# probe.net
KiCad netlist of a schematic drawn in EAGLE
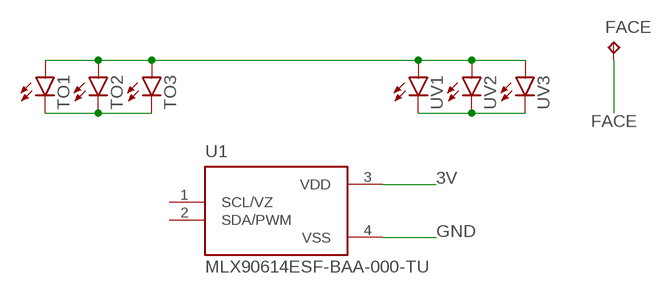
[diagram p0: schematic, sheet 1]

(export (version "E")
  (design (tool "Eeschema 10.0.6"))
  (components
    (comp (ref "FACE")
      (value "TPTP14R")
      (footprint "eagle-import:TP14R")
      (libsource (lib "eagle-import") (part "TPTP14R"))
    )
    (comp (ref "TO1")
      (value "LED5MM")
      (footprint "eagle-import:LED5MM")
      (libsource (lib "eagle-import") (part "LED5MM"))
    )
    (comp (ref "TO2")
      (value "LED5MM")
      (footprint "eagle-import:LED5MM")
      (libsource (lib "eagle-import") (part "LED5MM"))
    )
    (comp (ref "TO3")
      (value "LED5MM")
      (footprint "eagle-import:LED5MM")
      (libsource (lib "eagle-import") (part "LED5MM"))
    )
    (comp (ref "U1")
      (value "MLX90614ESF-BAA-000-TU")
      (footprint "eagle-import:TO254P942H425-4")
      (fields (field (name "MF") "Melexis"))
      (libsource (lib "eagle-import") (part "MLX90614ESF-BAA-000-TU"))
    )
    (comp (ref "UV1")
      (value "LED5MM")
      (footprint "eagle-import:LED5MM")
      (libsource (lib "eagle-import") (part "LED5MM"))
    )
    (comp (ref "UV2")
      (value "LED5MM")
      (footprint "eagle-import:LED5MM")
      (libsource (lib "eagle-import") (part "LED5MM"))
    )
    (comp (ref "UV3")
      (value "LED5MM")
      (footprint "eagle-import:LED5MM")
      (libsource (lib "eagle-import") (part "LED5MM"))
    )
  )
  (nets
    (net (code "1") (name "/3V") (class "Default")
      (node (ref "TO1") (pin "A") (pinfunction "A_A") (pintype "passive"))
      (node (ref "TO2") (pin "A") (pinfunction "A_A") (pintype "passive"))
      (node (ref "TO3") (pin "A") (pinfunction "A_A") (pintype "passive"))
      (node (ref "U1") (pin "3") (pinfunction "VDD_3") (pintype "power_in"))
      (node (ref "UV1") (pin "A") (pinfunction "A_A") (pintype "passive"))
      (node (ref "UV2") (pin "A") (pinfunction "A_A") (pintype "passive"))
      (node (ref "UV3") (pin "A") (pinfunction "A_A") (pintype "passive"))
    )
    (net (code "2") (name "/FACE") (class "Default")
      (node (ref "FACE") (pin "TP") (pinfunction "TP_TP") (pintype "input"))
    )
    (net (code "3") (name "/GND") (class "Default")
      (node (ref "U1") (pin "4") (pinfunction "VSS_4") (pintype "power_in"))
    )
    (net (code "4") (name "Net-(TO1-C)") (class "Default")
      (node (ref "TO1") (pin "K") (pinfunction "C_K") (pintype "passive"))
      (node (ref "TO2") (pin "K") (pinfunction "C_K") (pintype "passive"))
      (node (ref "TO3") (pin "K") (pinfunction "C_K") (pintype "passive"))
    )
    (net (code "5") (name "Net-(UV1-C)") (class "Default")
      (node (ref "UV1") (pin "K") (pinfunction "C_K") (pintype "passive"))
      (node (ref "UV2") (pin "K") (pinfunction "C_K") (pintype "passive"))
      (node (ref "UV3") (pin "K") (pinfunction "C_K") (pintype "passive"))
    )
    (net (code "6") (name "unconnected-(U1-SCL{slash}VZ-Pad1)") (class "Default")
      (node (ref "U1") (pin "1") (pinfunction "SCL/VZ_1") (pintype "input"))
    )
    (net (code "7") (name "unconnected-(U1-SDA{slash}PWM-Pad2)") (class "Default")
      (node (ref "U1") (pin "2") (pinfunction "SDA/PWM_2") (pintype "bidirectional"))
    )
  )
)
